# WIFI.net
KiCad netlist of a schematic drawn in Altium Designer
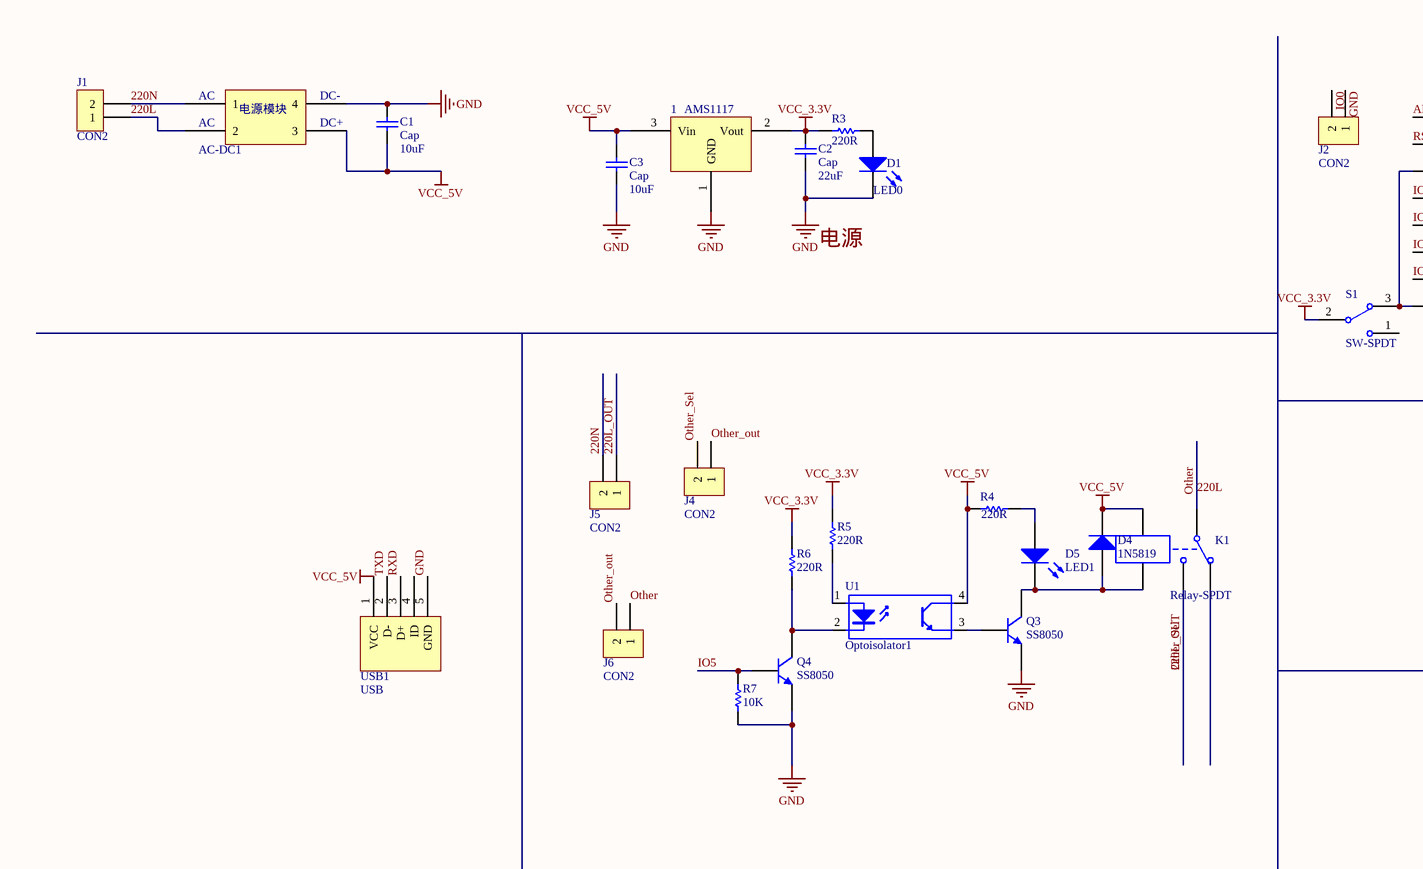
[diagram p0: WIFI.SchDoc, left]
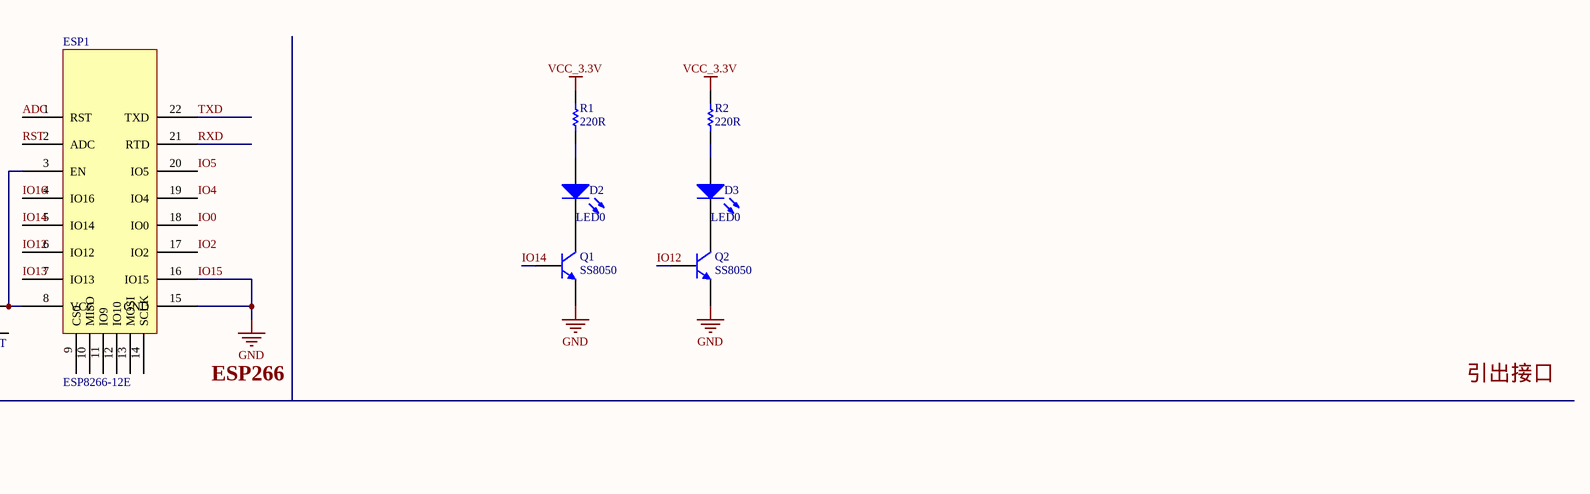
[diagram p1: WIFI.SchDoc, right]

(export (version "E")
  (design (tool "Eeschema 10.0.6"))
  (components
    (comp (ref "1") (value "AMS1117") (footprint "SOT223") (libsource (lib "开关电路") (part "AMS1117")))
    (comp (ref "AC-DC1") (value "220—5") (footprint "POWER-220_5") (libsource (lib "开关电路") (part "220—5")))
    (comp (ref "C1")
      (value "Cap")
      (footprint "CAP-E SMD 8X8")
      (description "Capacitor")
      (fields (field (name "ALTIUM_VALUE") "10uF") (field (name "PUBLISHER") "Altium Limited"))
      (libsource (lib "Miscellaneous Devices0") (part "Cap"))
    )
    (comp (ref "C2")
      (value "Cap")
      (footprint "1206")
      (description "Capacitor")
      (fields (field (name "ALTIUM_VALUE") "22uF") (field (name "PUBLISHER") "Altium Limited"))
      (libsource (lib "Miscellaneous Devices0") (part "Cap"))
    )
    (comp (ref "C3")
      (value "Cap")
      (footprint "1206")
      (description "Capacitor")
      (fields (field (name "ALTIUM_VALUE") "10uF") (field (name "PUBLISHER") "Altium Limited"))
      (libsource (lib "Miscellaneous Devices0") (part "Cap"))
    )
    (comp (ref "D1")
      (value "LED0")
      (footprint "ZH常用封装ZH:LED0805")
      (description "Typical INFRARED GaAs LED")
      (fields (field (name "PUBLISHER") "Altium Limited"))
      (libsource (lib "Miscellaneous Devices") (part "LED0"))
    )
    (comp (ref "D2")
      (value "LED0")
      (footprint "ZH常用封装ZH:LED0805")
      (description "Typical INFRARED GaAs LED")
      (fields (field (name "PUBLISHER") "Altium Limited"))
      (libsource (lib "Miscellaneous Devices") (part "LED0"))
    )
    (comp (ref "D3")
      (value "LED0")
      (footprint "ZH常用封装ZH:LED0805")
      (description "Typical INFRARED GaAs LED")
      (fields (field (name "PUBLISHER") "Altium Limited"))
      (libsource (lib "Miscellaneous Devices") (part "LED0"))
    )
    (comp (ref "D4")
      (value "1N5819")
      (footprint "ZH常用封装ZH:DO-214AC/SMA")
      (description "Default Diode")
      (fields (field (name "PUBLISHER") "Altium Limited"))
      (libsource (lib "Miscellaneous Devices") (part "Diode"))
    )
    (comp (ref "D5")
      (value "LED1")
      (footprint "ZH常用封装ZH:LED0805")
      (description "Typical RED GaAs LED")
      (fields (field (name "PUBLISHER") "Altium Limited"))
      (libsource (lib "Miscellaneous Devices") (part "LED1"))
    )
    (comp (ref "ESP1")
      (value "ESP8266-12E")
      (footprint "ZH常用封装ZH:ESP8266")
      (libsource (lib "开关电路") (part "ESP8266"))
    )
    (comp (ref "J1")
      (value "CON2")
      (footprint "TML-2-5.08")
      (description "Connector")
      (libsource (lib "") (part "CON2_1"))
    )
    (comp (ref "J2")
      (value "CON2")
      (footprint "HDR1X2")
      (description "Connector")
      (libsource (lib "插件") (part "CON2"))
    )
    (comp (ref "J4")
      (value "CON2")
      (footprint "HDR1X2")
      (description "Connector")
      (libsource (lib "插件") (part "CON2"))
    )
    (comp (ref "J5")
      (value "CON2")
      (footprint "TML-2-5.08")
      (description "Connector")
      (libsource (lib "插件") (part "CON2"))
    )
    (comp (ref "J6")
      (value "CON2")
      (footprint "TML-2-5.08")
      (description "Connector")
      (libsource (lib "插件") (part "CON2"))
    )
    (comp (ref "K1")
      (value "Relay-SPDT")
      (footprint "5V-5")
      (description "Single-Pole Dual-Throw Relay")
      (fields (field (name "PUBLISHER") "Altium Limited"))
      (libsource (lib "Miscellaneous Devices") (part "Relay-SPDT"))
    )
    (comp (ref "Q1")
      (value "SS8050")
      (footprint "SOT-23")
      (description "NPN General Purpose Amplifier")
      (fields (field (name "PUBLISHER") "Altium Limited"))
      (libsource (lib "Miscellaneous Devices") (part "2N3904"))
    )
    (comp (ref "Q2")
      (value "SS8050")
      (footprint "SOT-23")
      (description "NPN General Purpose Amplifier")
      (fields (field (name "PUBLISHER") "Altium Limited"))
      (libsource (lib "Miscellaneous Devices") (part "2N3904"))
    )
    (comp (ref "Q3")
      (value "SS8050")
      (footprint "SOT-23")
      (description "NPN General Purpose Amplifier")
      (fields (field (name "PUBLISHER") "Altium Limited"))
      (libsource (lib "Miscellaneous Devices") (part "2N3904"))
    )
    (comp (ref "Q4")
      (value "SS8050")
      (footprint "SOT-23")
      (description "NPN General Purpose Amplifier")
      (fields (field (name "PUBLISHER") "Altium Limited"))
      (libsource (lib "Miscellaneous Devices") (part "2N3904"))
    )
    (comp (ref "R1")
      (value "220R")
      (footprint "贴片:0805")
      (description "Resistor")
      (fields (field (name "Comment") "Res") (field (name "PUBLISHER") "Altium Limited"))
      (libsource (lib "电阻电容") (part "Res"))
    )
    (comp (ref "R2")
      (value "220R")
      (footprint "贴片:0805")
      (description "Resistor")
      (fields (field (name "Comment") "Res") (field (name "PUBLISHER") "Altium Limited"))
      (libsource (lib "电阻电容") (part "Res"))
    )
    (comp (ref "R3")
      (value "220R")
      (footprint "贴片:0805")
      (description "Resistor")
      (fields (field (name "Comment") "Res") (field (name "PUBLISHER") "Altium Limited"))
      (libsource (lib "电阻电容") (part "Res"))
    )
    (comp (ref "R4")
      (value "220R")
      (footprint "贴片:0805")
      (description "Resistor")
      (fields (field (name "Comment") "Res") (field (name "PUBLISHER") "Altium Limited"))
      (libsource (lib "电阻电容") (part "Res"))
    )
    (comp (ref "R5")
      (value "220R")
      (footprint "贴片:0805")
      (description "Resistor")
      (fields (field (name "Comment") "Res") (field (name "PUBLISHER") "Altium Limited"))
      (libsource (lib "电阻电容") (part "Res"))
    )
    (comp (ref "R6")
      (value "220R")
      (footprint "贴片:0805")
      (description "Resistor")
      (fields (field (name "Comment") "Res") (field (name "PUBLISHER") "Altium Limited"))
      (libsource (lib "电阻电容") (part "Res"))
    )
    (comp (ref "R7")
      (value "10K")
      (footprint "贴片:0805")
      (description "Resistor")
      (fields (field (name "Comment") "Res") (field (name "PUBLISHER") "Altium Limited"))
      (libsource (lib "电阻电容") (part "Res"))
    )
    (comp (ref "S1")
      (value "SW-SPDT")
      (footprint "SS12D00G3")
      (description "SPDT Subminiature Toggle Switch, Right Angle Mounting, Vertical Actuation")
      (fields (field (name "PUBLISHER") "Altium Limited"))
      (libsource (lib "Miscellaneous Devices") (part "SW-SPDT"))
    )
    (comp (ref "U1")
      (value "Optoisolator1")
      (footprint "DIP4")
      (description "4-Pin Phototransistor Optocoupler")
      (fields (field (name "PUBLISHER") "Altium Limited"))
      (libsource (lib "Miscellaneous Devices") (part "Optoisolator1"))
    )
    (comp (ref "USB1")
      (value "USB")
      (footprint "ZH常用封装ZH:USB-MINI")
      (libsource (lib "CH340") (part "miniUSB-b"))
    )
  )
  (nets
    (net (code "1") (name "/220L") (class "Default")
      (node (ref "AC-DC1") (pin "2") (pinfunction "2_2") (pintype "passive"))
      (node (ref "J1") (pin "1") (pinfunction "1_1") (pintype "passive"))
      (node (ref "J6") (pin "1") (pinfunction "1_1") (pintype "passive"))
      (node (ref "K1") (pin "1") (pinfunction "1_1") (pintype "passive"))
    )
    (net (code "2") (name "/220L_OUT") (class "Default")
      (node (ref "J4") (pin "2") (pinfunction "2_2") (pintype "passive"))
      (node (ref "J5") (pin "1") (pinfunction "1_1") (pintype "passive"))
      (node (ref "K1") (pin "3") (pinfunction "3_3") (pintype "passive"))
    )
    (net (code "3") (name "/220N") (class "Default")
      (node (ref "AC-DC1") (pin "1") (pinfunction "1_1") (pintype "passive"))
      (node (ref "J1") (pin "2") (pinfunction "2_2") (pintype "passive"))
      (node (ref "J5") (pin "2") (pinfunction "2_2") (pintype "passive"))
    )
    (net (code "5") (name "/ADC") (class "Default")
      (node (ref "ESP1") (pin "1") (pinfunction "RST_1") (pintype "passive"))
    )
    (net (code "7") (name "/IO0") (class "Default")
      (node (ref "ESP1") (pin "18") (pinfunction "IO0_18") (pintype "passive"))
      (node (ref "J2") (pin "2") (pinfunction "2_2") (pintype "passive"))
    )
    (net (code "8") (name "/IO2") (class "Default")
      (node (ref "ESP1") (pin "17") (pinfunction "IO2_17") (pintype "passive"))
    )
    (net (code "9") (name "/IO4") (class "Default")
      (node (ref "ESP1") (pin "19") (pinfunction "IO4_19") (pintype "passive"))
    )
    (net (code "10") (name "/IO5") (class "Default")
      (node (ref "ESP1") (pin "20") (pinfunction "IO5_20") (pintype "passive"))
      (node (ref "Q4") (pin "2") (pinfunction "B_2") (pintype "passive"))
      (node (ref "R7") (pin "2") (pinfunction "2_2") (pintype "passive"))
    )
    (net (code "11") (name "/IO12") (class "Default")
      (node (ref "ESP1") (pin "6") (pinfunction "IO12_6") (pintype "passive"))
      (node (ref "Q2") (pin "2") (pinfunction "B_2") (pintype "passive"))
    )
    (net (code "12") (name "/IO13") (class "Default")
      (node (ref "ESP1") (pin "7") (pinfunction "IO13_7") (pintype "passive"))
    )
    (net (code "13") (name "/IO14") (class "Default")
      (node (ref "ESP1") (pin "5") (pinfunction "IO14_5") (pintype "passive"))
      (node (ref "Q1") (pin "2") (pinfunction "B_2") (pintype "passive"))
    )
    (net (code "14") (name "/IO16") (class "Default")
      (node (ref "ESP1") (pin "4") (pinfunction "IO16_4") (pintype "passive"))
    )
    (net (code "15") (name "/Other_out") (class "Default")
      (node (ref "J4") (pin "1") (pinfunction "1_1") (pintype "passive"))
      (node (ref "J6") (pin "2") (pinfunction "2_2") (pintype "passive"))
    )
    (net (code "16") (name "/RST") (class "Default")
      (node (ref "ESP1") (pin "2") (pinfunction "ADC_2") (pintype "passive"))
    )
    (net (code "17") (name "/RXD") (class "Default")
      (node (ref "ESP1") (pin "21") (pinfunction "RTD_21") (pintype "passive"))
      (node (ref "USB1") (pin "3") (pinfunction "D+_3") (pintype "passive"))
    )
    (net (code "18") (name "/TXD") (class "Default")
      (node (ref "ESP1") (pin "22") (pinfunction "TXD_22") (pintype "passive"))
      (node (ref "USB1") (pin "2") (pinfunction "D-_2") (pintype "passive"))
    )
    (net (code "21") (name "GND") (class "Default")
      (node (ref "1") (pin "1") (pinfunction "GND_1") (pintype "passive"))
      (node (ref "AC-DC1") (pin "4") (pinfunction "4_4") (pintype "passive"))
      (node (ref "C1") (pin "1") (pinfunction "1_1") (pintype "passive"))
      (node (ref "C2") (pin "2") (pinfunction "2_2") (pintype "passive"))
      (node (ref "C3") (pin "2") (pinfunction "2_2") (pintype "passive"))
      (node (ref "D1") (pin "2") (pinfunction "K_2") (pintype "passive"))
      (node (ref "ESP1") (pin "15") (pinfunction "GND_15") (pintype "passive"))
      (node (ref "ESP1") (pin "16") (pinfunction "IO15_16") (pintype "passive"))
      (node (ref "J2") (pin "1") (pinfunction "1_1") (pintype "passive"))
      (node (ref "Q1") (pin "1") (pinfunction "E_1") (pintype "passive"))
      (node (ref "Q2") (pin "1") (pinfunction "E_1") (pintype "passive"))
      (node (ref "Q3") (pin "1") (pinfunction "E_1") (pintype "passive"))
      (node (ref "Q4") (pin "1") (pinfunction "E_1") (pintype "passive"))
      (node (ref "R7") (pin "1") (pinfunction "1_1") (pintype "passive"))
      (node (ref "USB1") (pin "5") (pinfunction "GND_5") (pintype "passive"))
    )
    (net (code "22") (name "Net-(D1-A)") (class "Default")
      (node (ref "D1") (pin "1") (pinfunction "A_1") (pintype "passive"))
      (node (ref "R3") (pin "1") (pinfunction "1_1") (pintype "passive"))
    )
    (net (code "23") (name "Net-(D2-A)") (class "Default")
      (node (ref "D2") (pin "1") (pinfunction "A_1") (pintype "passive"))
      (node (ref "R1") (pin "2") (pinfunction "2_2") (pintype "passive"))
    )
    (net (code "24") (name "Net-(D2-K)") (class "Default")
      (node (ref "D2") (pin "2") (pinfunction "K_2") (pintype "passive"))
      (node (ref "Q1") (pin "3") (pinfunction "C_3") (pintype "passive"))
    )
    (net (code "25") (name "Net-(D3-A)") (class "Default")
      (node (ref "D3") (pin "1") (pinfunction "A_1") (pintype "passive"))
      (node (ref "R2") (pin "2") (pinfunction "2_2") (pintype "passive"))
    )
    (net (code "26") (name "Net-(D3-K)") (class "Default")
      (node (ref "D3") (pin "2") (pinfunction "K_2") (pintype "passive"))
      (node (ref "Q2") (pin "3") (pinfunction "C_3") (pintype "passive"))
    )
    (net (code "27") (name "Net-(D4-A)") (class "Default")
      (node (ref "D4") (pin "1") (pinfunction "A_1") (pintype "passive"))
      (node (ref "D5") (pin "2") (pinfunction "K_2") (pintype "passive"))
      (node (ref "K1") (pin "5") (pinfunction "5_5") (pintype "passive"))
      (node (ref "Q3") (pin "3") (pinfunction "C_3") (pintype "passive"))
    )
    (net (code "28") (name "Net-(D5-A)") (class "Default")
      (node (ref "D5") (pin "1") (pinfunction "A_1") (pintype "passive"))
      (node (ref "R4") (pin "2") (pinfunction "2_2") (pintype "passive"))
    )
    (net (code "29") (name "Net-(ESP1-EN)") (class "Default")
      (node (ref "ESP1") (pin "3") (pinfunction "EN_3") (pintype "passive"))
      (node (ref "ESP1") (pin "8") (pinfunction "VCC_8") (pintype "passive"))
      (node (ref "S1") (pin "3") (pinfunction "3_3") (pintype "passive"))
    )
    (net (code "30") (name "Net-(Q3-B)") (class "Default")
      (node (ref "Q3") (pin "2") (pinfunction "B_2") (pintype "passive"))
      (node (ref "U1") (pin "3") (pinfunction "E_3") (pintype "passive"))
    )
    (net (code "31") (name "Net-(Q4-C)") (class "Default")
      (node (ref "Q4") (pin "3") (pinfunction "C_3") (pintype "passive"))
      (node (ref "R6") (pin "1") (pinfunction "1_1") (pintype "passive"))
      (node (ref "U1") (pin "2") (pinfunction "K_2") (pintype "passive"))
    )
    (net (code "32") (name "Net-(U1-A)") (class "Default")
      (node (ref "R5") (pin "1") (pinfunction "1_1") (pintype "passive"))
      (node (ref "U1") (pin "1") (pinfunction "A_1") (pintype "passive"))
    )
    (net (code "33") (name "VCC_3.3V") (class "Default")
      (node (ref "1") (pin "2") (pinfunction "Vout_2") (pintype "passive"))
      (node (ref "C2") (pin "1") (pinfunction "1_1") (pintype "passive"))
      (node (ref "R1") (pin "1") (pinfunction "1_1") (pintype "passive"))
      (node (ref "R2") (pin "1") (pinfunction "1_1") (pintype "passive"))
      (node (ref "R3") (pin "2") (pinfunction "2_2") (pintype "passive"))
      (node (ref "R5") (pin "2") (pinfunction "2_2") (pintype "passive"))
      (node (ref "R6") (pin "2") (pinfunction "2_2") (pintype "passive"))
      (node (ref "S1") (pin "2") (pinfunction "2_2") (pintype "passive"))
    )
    (net (code "34") (name "VCC_5V") (class "Default")
      (node (ref "1") (pin "3") (pinfunction "Vin_3") (pintype "passive"))
      (node (ref "AC-DC1") (pin "3") (pinfunction "3_3") (pintype "passive"))
      (node (ref "C1") (pin "2") (pinfunction "2_2") (pintype "passive"))
      (node (ref "C3") (pin "1") (pinfunction "1_1") (pintype "passive"))
      (node (ref "D4") (pin "2") (pinfunction "K_2") (pintype "passive"))
      (node (ref "K1") (pin "4") (pinfunction "4_4") (pintype "passive"))
      (node (ref "R4") (pin "1") (pinfunction "1_1") (pintype "passive"))
      (node (ref "U1") (pin "4") (pinfunction "C_4") (pintype "passive"))
      (node (ref "USB1") (pin "1") (pinfunction "VCC_1") (pintype "passive"))
    )
    (net (code "35") (name "unconnected-(ESP1-CS0-Pad9)") (class "Default")
      (node (ref "ESP1") (pin "9") (pinfunction "CS0_9") (pintype "passive"))
    )
    (net (code "36") (name "unconnected-(ESP1-IO9-Pad11)") (class "Default")
      (node (ref "ESP1") (pin "11") (pinfunction "IO9_11") (pintype "passive"))
    )
    (net (code "37") (name "unconnected-(ESP1-IO10-Pad12)") (class "Default")
      (node (ref "ESP1") (pin "12") (pinfunction "IO10_12") (pintype "passive"))
    )
    (net (code "38") (name "unconnected-(ESP1-MISO-Pad10)") (class "Default")
      (node (ref "ESP1") (pin "10") (pinfunction "MISO_10") (pintype "passive"))
    )
    (net (code "39") (name "unconnected-(ESP1-MOSI-Pad13)") (class "Default")
      (node (ref "ESP1") (pin "13") (pinfunction "MOSI_13") (pintype "passive"))
    )
    (net (code "40") (name "unconnected-(ESP1-SCLK-Pad14)") (class "Default")
      (node (ref "ESP1") (pin "14") (pinfunction "SCLK_14") (pintype "passive"))
    )
    (net (code "41") (name "unconnected-(K1-Pad2)") (class "Default")
      (node (ref "K1") (pin "2") (pinfunction "2_2") (pintype "passive"))
    )
    (net (code "42") (name "unconnected-(S1-Pad1)") (class "Default")
      (node (ref "S1") (pin "1") (pinfunction "1_1") (pintype "passive"))
    )
    (net (code "43") (name "unconnected-(USB1-ID-Pad4)") (class "Default")
      (node (ref "USB1") (pin "4") (pinfunction "ID_4") (pintype "passive"))
    )
  )
)
